# Thunder-Refix.net
KiCad netlist of a schematic drawn in Altium Designer
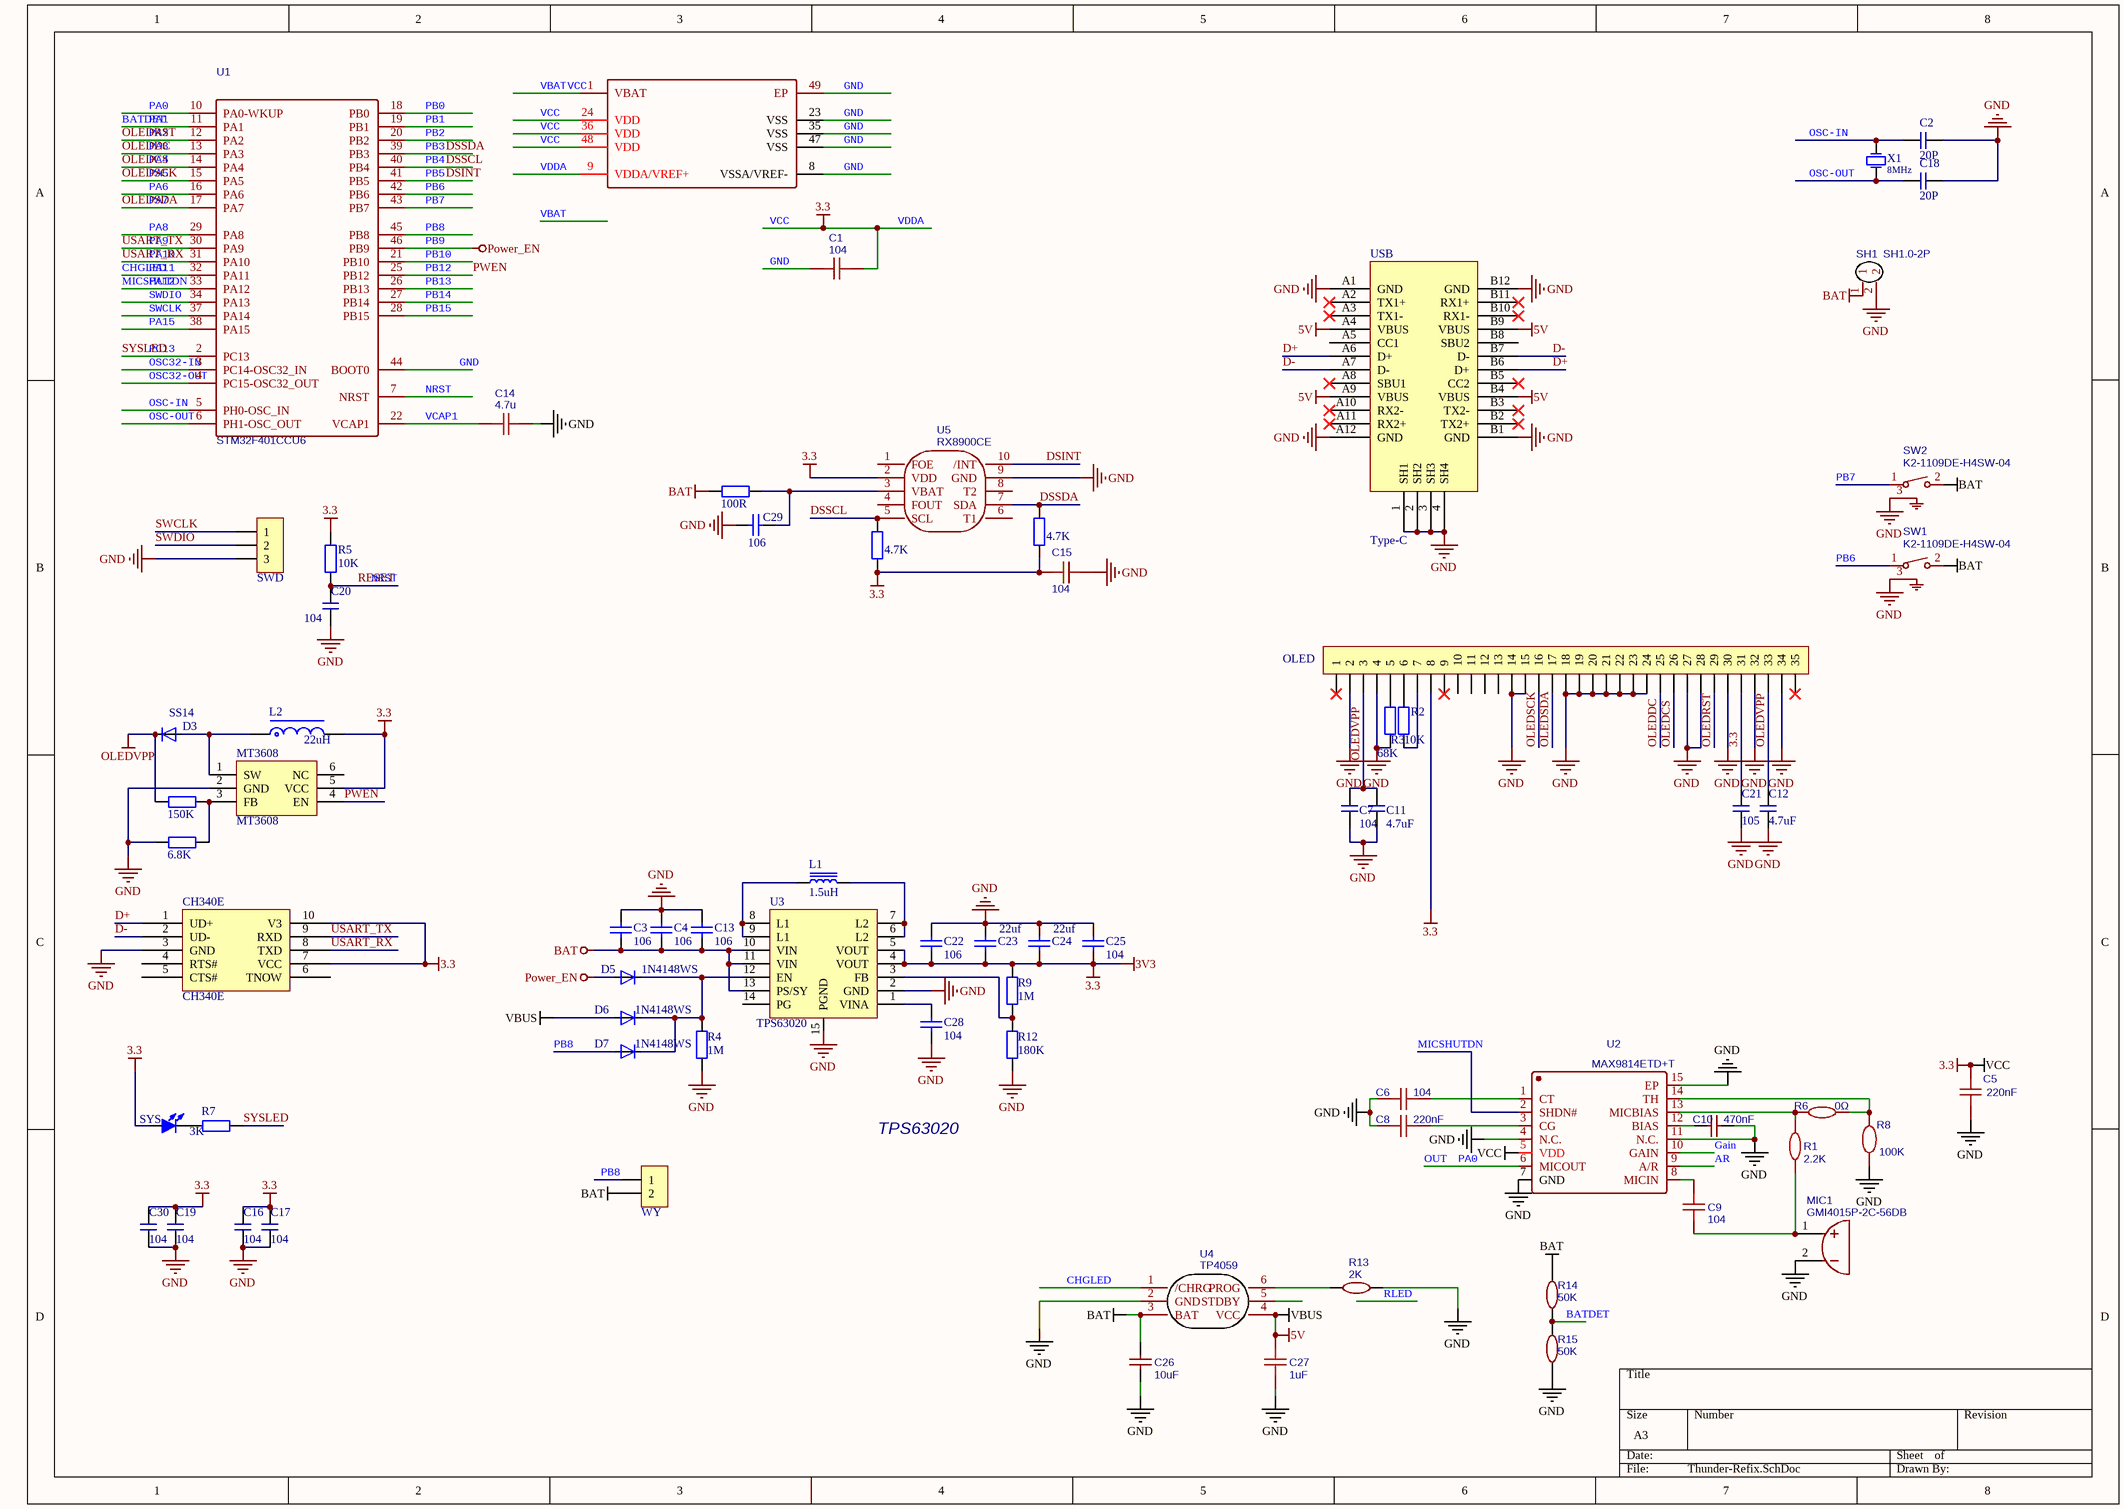
[diagram p0: Thunder-Refix.SchDoc]

(export (version "E")
  (design (tool "Eeschema 10.0.6"))
  (components
    (comp (ref "C1")
      (value "104")
      (footprint "0603C")
      (fields (field (name "CONTRIBUTOR") "LCEDA_Lib"))
      (libsource (lib "altium-import") (part "root_2_0.1u_"))
    )
    (comp (ref "C2") (value "20P") (footprint "0603C") (libsource (lib "Schlib1") (part "电容")))
    (comp (ref "C3")
      (value "106")
      (footprint "我的PCB库:0603c")
      (fields (field (name "C") "106"))
      (libsource (lib "元件库") (part "cap"))
    )
    (comp (ref "C4")
      (value "106")
      (footprint "我的PCB库:0603c")
      (fields (field (name "C") "106"))
      (libsource (lib "元件库") (part "cap"))
    )
    (comp (ref "C5")
      (value "220nF")
      (footprint "0603c")
      (fields
        (field (name "BOM_SUPPLIER PART") "C354366")
        (field (name "BOM_MANUFACTURER PART") "GCJ21BR71H224KA01L")
        (field (name "CONTRIBUTOR") "LCSC")
      )
      (libsource (lib "altium-import") (part "root_1_220nF_"))
    )
    (comp (ref "C6")
      (value "104")
      (footprint "0603c")
      (fields
        (field (name "BOM_SUPPLIER PART") "C444732")
        (field (name "BOM_MANUFACTURER PART") "FS055C104K4Z2A")
        (field (name "CONTRIBUTOR") "LCSC")
      )
      (libsource (lib "altium-import") (part "root_1_100nF_"))
    )
    (comp (ref "C7") (value "104") (footprint "0603C") (libsource (lib "Schlib1") (part "电容")))
    (comp (ref "C8")
      (value "220nF")
      (footprint "0603c")
      (fields
        (field (name "BOM_SUPPLIER PART") "C354366")
        (field (name "BOM_MANUFACTURER PART") "GCJ21BR71H224KA01L")
        (field (name "CONTRIBUTOR") "LCSC")
      )
      (libsource (lib "altium-import") (part "root_0_220nF_"))
    )
    (comp (ref "C9")
      (value "104")
      (footprint "0603c")
      (fields
        (field (name "BOM_SUPPLIER PART") "C444732")
        (field (name "BOM_MANUFACTURER PART") "FS055C104K4Z2A")
        (field (name "CONTRIBUTOR") "LCSC")
      )
      (libsource (lib "altium-import") (part "root_0_100nF_"))
    )
    (comp (ref "C10")
      (value "470nF")
      (footprint "0603c")
      (fields
        (field (name "BOM_MANUFACTURER PART") "CL21B474KBFNNNE")
        (field (name "BOM_SUPPLIER PART") "C13967")
      )
      (libsource (lib "altium-import") (part "root_0_470nF_"))
    )
    (comp (ref "C11") (value "4.7uF") (footprint "0603C") (libsource (lib "Schlib1") (part "电容")))
    (comp (ref "C12") (value "4.7uF") (footprint "0603C") (libsource (lib "Schlib1") (part "电容")))
    (comp (ref "C13")
      (value "106")
      (footprint "0603c")
      (fields (field (name "C") "106"))
      (libsource (lib "元件库") (part "cap"))
    )
    (comp (ref "C14")
      (value "4.7u")
      (footprint "0603C")
      (fields (field (name "CONTRIBUTOR") "LCEDA_Lib"))
      (libsource (lib "altium-import") (part "root_0_4.7u_"))
    )
    (comp (ref "C15")
      (value "104")
      (footprint "0603C")
      (fields (field (name "CONTRIBUTOR") "LCEDA_Lib"))
      (libsource (lib "altium-import") (part "root_0_0.1u_"))
    )
    (comp (ref "C16") (value "104") (footprint "0603C") (libsource (lib "Schlib1") (part "电容")))
    (comp (ref "C17") (value "104") (footprint "0603C") (libsource (lib "Schlib1") (part "电容")))
    (comp (ref "C18") (value "20P") (footprint "0603C") (libsource (lib "Schlib1") (part "电容")))
    (comp (ref "C19") (value "104") (footprint "0603C") (libsource (lib "Schlib1") (part "电容")))
    (comp (ref "C20") (value "104") (footprint "0603C") (libsource (lib "Schlib1") (part "电容")))
    (comp (ref "C21") (value "105") (footprint "0603C") (libsource (lib "Schlib1") (part "电容")))
    (comp (ref "C22")
      (value "106")
      (footprint "0603c")
      (fields (field (name "C") "106"))
      (libsource (lib "元件库") (part "cap"))
    )
    (comp (ref "C23")
      (value "22uf")
      (footprint "0603c")
      (fields (field (name "C") "22uf"))
      (libsource (lib "元件库") (part "cap"))
    )
    (comp (ref "C24")
      (value "22uf")
      (footprint "0603c")
      (fields (field (name "C") "22uf"))
      (libsource (lib "元件库") (part "cap"))
    )
    (comp (ref "C25")
      (value "104")
      (footprint "0603c")
      (fields (field (name "C") "104"))
      (libsource (lib "元件库") (part "cap"))
    )
    (comp (ref "C26")
      (value "10uF")
      (footprint "0603c")
      (fields
        (field (name "BOM_SUPPLIER PART") "C162317")
        (field (name "BOM_MANUFACTURER PART") "GRM21BB31C106KE15L")
        (field (name "CONTRIBUTOR") "LCSC")
      )
      (libsource (lib "altium-import") (part "root_1_10uF_"))
    )
    (comp (ref "C27")
      (value "1uF")
      (footprint "0603c")
      (fields
        (field (name "BOM_SUPPLIER PART") "C319195")
        (field (name "BOM_MANUFACTURER PART") "UMK212BJ105KG-T")
        (field (name "CONTRIBUTOR") "LCSC")
      )
      (libsource (lib "altium-import") (part "root_1_1uF_"))
    )
    (comp (ref "C28")
      (value "104")
      (footprint "0603c")
      (fields (field (name "C") "104"))
      (libsource (lib "元件库") (part "cap"))
    )
    (comp (ref "C29")
      (value "106")
      (footprint "0603c")
      (fields (field (name "C") "106"))
      (libsource (lib "元件库") (part "cap"))
    )
    (comp (ref "C30") (value "104") (footprint "0603C") (libsource (lib "Schlib1") (part "电容")))
    (comp (ref "CH340E") (value "CH340E") (footprint "MSOP10_L") (libsource (lib "CUBE_T1") (part "CH340E")))
    (comp (ref "D3")
      (value "SS14")
      (footprint "SOD323_1N4148WS")
      (description "Diode Switching 75V 0.3A 2-Pin SOD-323 T/R")
      (fields (field (name "MF") "ON Semiconductor") (field (name "MP") "1N4148WS"))
      (libsource (lib "1N4148WS") (part "1N4148WS"))
    )
    (comp (ref "D5")
      (value "1N4148WS")
      (footprint "SOD323_1N4148WS")
      (description "Diode Switching 75V 0.3A 2-Pin SOD-323 T/R")
      (fields (field (name "MF") "ON Semiconductor"))
      (libsource (lib "1N4148WS") (part "1N4148WS"))
    )
    (comp (ref "D6")
      (value "1N4148WS")
      (footprint "SOD323_1N4148WS")
      (description "Diode Switching 75V 0.3A 2-Pin SOD-323 T/R")
      (fields (field (name "MF") "ON Semiconductor"))
      (libsource (lib "1N4148WS") (part "1N4148WS"))
    )
    (comp (ref "D7")
      (value "1N4148WS")
      (footprint "SOD323_1N4148WS")
      (description "Diode Switching 75V 0.3A 2-Pin SOD-323 T/R")
      (fields (field (name "MF") "ON Semiconductor"))
      (libsource (lib "1N4148WS") (part "1N4148WS"))
    )
    (comp (ref "L1")
      (value "1.5uH")
      (footprint "我的PCB库:IND-SMD_L3.0-W3.0_NR3010")
      (fields (field (name "_VALUE") "1.5uH"))
      (libsource (lib "元件库") (part "Inductor Iron 2"))
    )
    (comp (ref "L2")
      (value "22uH")
      (footprint "IND-SMD_L3.0-W3.0_NR3010")
      (description "功率屏蔽电感")
      (fields (field (name "版权归属") "源创客"))
      (libsource (lib "3.1   - 电阻-电容-电感") (part "L-CDRH"))
    )
    (comp (ref "MIC1")
      (value "GMI4015P-2C-56DB")
      (footprint "MIC-TH_BD4.0-P2.00-D0.4-L-FD")
      (fields
        (field (name "BOM_SUPPLIER PART") "C233299")
        (field (name "BOM_MANUFACTURER PART") "GMI4015P-2C-56db")
        (field (name "CONTRIBUTOR") "LCSC")
      )
      (libsource (lib "altium-import") (part "root_0_GMI4015P-2C-56DB_"))
    )
    (comp (ref "MT3608")
      (value "MT3608")
      (footprint "SOT23-6N")
      (description "可调升压芯片")
      (fields (field (name "版权归属") "源创客"))
      (libsource (lib "1.3   - 电源类芯片") (part "SX1308"))
    )
    (comp (ref "OLED")
      (value "FPC1.0-35P")
      (footprint "1.69 OLED")
      (description "FPC连接器")
      (fields (field (name "版权归属") "源创客"))
      (libsource (lib "4.14 - FPC连接器") (part "FPC-35P"))
    )
    (comp (ref "R1")
      (value "2.2K")
      (footprint "0603r")
      (fields
        (field (name "BOM_SUPPLIER PART") "C325769")
        (field (name "BOM_MANUFACTURER PART") "RMC08052.2K1%N")
        (field (name "CONTRIBUTOR") "LCSC")
      )
      (libsource (lib "altium-import") (part "root_1_2.2K_"))
    )
    (comp (ref "R2")
      (value "10K")
      (footprint "0603R")
      (description "贴片电阻")
      (fields (field (name "版权归属") "源创客"))
      (libsource (lib "3.1   - 电阻-电容-电感") (part "R"))
    )
    (comp (ref "R3")
      (value "68K")
      (footprint "0603R")
      (description "贴片电阻")
      (fields (field (name "版权归属") "源创客"))
      (libsource (lib "3.1   - 电阻-电容-电感") (part "R"))
    )
    (comp (ref "R4")
      (value "1M")
      (footprint "0603r")
      (fields (field (name "R") "1M"))
      (libsource (lib "元件库") (part "Res"))
    )
    (comp (ref "R5")
      (value "10K")
      (footprint "0603R")
      (description "贴片电阻")
      (fields (field (name "版权归属") "源创客"))
      (libsource (lib "3.1   - 电阻-电容-电感") (part "R"))
    )
    (comp (ref "R6")
      (value "0Ω")
      (footprint "0603r")
      (fields
        (field (name "BOM_SUPPLIER PART") "C325765")
        (field (name "BOM_MANUFACTURER PART") "RMC0805150K1%N")
        (field (name "CONTRIBUTOR") "LCSC")
      )
      (libsource (lib "altium-import") (part "root_0_150K_"))
    )
    (comp (ref "R7")
      (value "3K")
      (footprint "0603R")
      (description "贴片电阻")
      (fields (field (name "版权归属") "源创客"))
      (libsource (lib "3.1   - 电阻-电容-电感") (part "R"))
    )
    (comp (ref "R8")
      (value "100K")
      (footprint "0603r")
      (fields
        (field (name "BOM_SUPPLIER PART") "C346756")
        (field (name "BOM_MANUFACTURER PART") "RTAN0805BKE100K")
        (field (name "CONTRIBUTOR") "LCSC")
      )
      (libsource (lib "altium-import") (part "root_1_100K_"))
    )
    (comp (ref "R9")
      (value "1M")
      (footprint "0603r")
      (fields (field (name "R") "1M"))
      (libsource (lib "元件库") (part "Res"))
    )
    (comp (ref "R10")
      (value "4.7K")
      (footprint "0603R")
      (description "贴片电阻")
      (fields (field (name "版权归属") "源创客"))
      (libsource (lib "3.1   - 电阻-电容-电感") (part "R"))
    )
    (comp (ref "R11")
      (value "4.7K")
      (footprint "0603R")
      (description "贴片电阻")
      (fields (field (name "版权归属") "源创客"))
      (libsource (lib "3.1   - 电阻-电容-电感") (part "R"))
    )
    (comp (ref "R12")
      (value "180K")
      (footprint "0603r")
      (fields (field (name "R") "180K"))
      (libsource (lib "元件库") (part "Res"))
    )
    (comp (ref "R13")
      (value "2K")
      (footprint "0603r")
      (fields
        (field (name "BOM_MANUFACTURER PART") "RC0603FR-071K5L")
        (field (name "BOM_SUPPLIER PART") "C114668")
      )
      (libsource (lib "altium-import") (part "root_0_1.5K_"))
    )
    (comp (ref "R14")
      (value "50K")
      (footprint "0603r")
      (fields
        (field (name "BOM_MANUFACTURER PART") "RC0603FR-071K5L")
        (field (name "BOM_SUPPLIER PART") "C114668")
      )
      (libsource (lib "altium-import") (part "root_1_1.5K_"))
    )
    (comp (ref "R15")
      (value "50K")
      (footprint "0603r")
      (fields
        (field (name "BOM_MANUFACTURER PART") "RC0603FR-071K5L")
        (field (name "BOM_SUPPLIER PART") "C114668")
      )
      (libsource (lib "altium-import") (part "root_1_1.5K_"))
    )
    (comp (ref "R16")
      (value "100R")
      (footprint "0603R")
      (description "贴片电阻")
      (fields (field (name "版权归属") "源创客"))
      (libsource (lib "3.1   - 电阻-电容-电感") (part "R"))
    )
    (comp (ref "RB")
      (value "150K")
      (footprint "0603R")
      (description "贴片电阻")
      (fields (field (name "版权归属") "源创客"))
      (libsource (lib "3.1   - 电阻-电容-电感") (part "R"))
    )
    (comp (ref "RS")
      (value "6.8K")
      (footprint "0603R")
      (description "贴片电阻")
      (fields (field (name "版权归属") "源创客"))
      (libsource (lib "3.1   - 电阻-电容-电感") (part "R"))
    )
    (comp (ref "SH1")
      (value "SH1.0-2P")
      (footprint "SH1.0")
      (fields (field (name "CONTRIBUTOR") "perry2867"))
      (libsource (lib "altium-import") (part "root_1_SH1.0-2P_"))
    )
    (comp (ref "SW1")
      (value "K2-1109DE-H4SW-04")
      (footprint "KEY-TH_K2-1109DE-CXXW-XX")
      (fields (field (name "BOM_SUPPLIER PART") "C961730") (field (name "CONTRIBUTOR") "LCSC"))
      (libsource (lib "altium-import") (part "root_0_K2-1109DE-H4SW-04_"))
    )
    (comp (ref "SW2")
      (value "K2-1109DE-H4SW-04")
      (footprint "KEY-TH_K2-1109DE-CXXW-XX")
      (fields (field (name "BOM_SUPPLIER PART") "C961730") (field (name "CONTRIBUTOR") "LCSC"))
      (libsource (lib "altium-import") (part "root_0_K2-1109DE-H4SW-04_"))
    )
    (comp (ref "SWD")
      (value "HDR-1X3")
      (footprint "ZH1.5-LI-3P")
      (description "3P接插件")
      (fields (field (name "版权归属") "源创客"))
      (libsource (lib "4.3   - 接插件-脚距1.5") (part "Header 3"))
    )
    (comp (ref "SYS")
      (value "粉色")
      (footprint "0603LED")
      (description "方形LED")
      (fields (field (name "版权归属") "源创客"))
      (libsource (lib "9.1   - LED") (part "LED-F234"))
    )
    (comp (ref "U1")
      (value "STM32F401CCU6")
      (footprint "qfn48")
      (fields (field (name "BOM_SUPPLIER PART") "C79861") (field (name "SUBPART_NO") "1"))
      (libsource (lib "Galaxy") (part "STM32F401CCU6"))
    )
    (comp (ref "U2")
      (value "MAX9814ETD+T")
      (footprint "TDFN-14_L3.0-W3.0-P0.40-BL-EP")
      (fields (field (name "BOM_SUPPLIER PART") "C41714"))
      (libsource (lib "altium-import") (part "root_0_MAX9814ETD+T_"))
    )
    (comp (ref "U3")
      (value "TPS63020")
      (footprint "我的PCB库:TPS63020")
      (libsource (lib "我的元件库") (part "TPS63020"))
    )
    (comp (ref "U4")
      (value "TP4059")
      (footprint "SOT23-6N")
      (fields (field (name "BOM_SUPPLIER PART") "C80364"))
      (libsource (lib "altium-import") (part "root_0_TP4059_"))
    )
    (comp (ref "U5")
      (value "RX8900CE")
      (footprint "RX8130")
      (fields (field (name "CONTRIBUTOR") "SudoMaker"))
      (libsource (lib "altium-import") (part "root_0_RX8900CE_"))
    )
    (comp (ref "USB") (value "Type-C") (footprint "Type-C") (libsource (lib "元件") (part "Type-C")))
    (comp (ref "WY")
      (value "HDR-1X2")
      (footprint "MX 1.25-WI-2P")
      (description "2P接插件")
      (fields (field (name "版权归属") "源创客"))
      (libsource (lib "4.2   - 接插件-脚距1.25") (part "Header 2"))
    )
    (comp (ref "X1")
      (value "8MHz")
      (footprint "OSC 5032-2P")
      (description "XTAL,8MHz,±20PPM,12.6*4.5")
      (fields (field (name "Comment") "1.6.1.01.005.001"))
      (libsource (lib "Mark_7") (part "1.6.1.01.005.001"))
    )
  )
  (nets
    (net (code "1") (name "/AR") (class "Default")
      (node (ref "U2") (pin "9") (pinfunction "A/R_9") (pintype "passive"))
    )
    (net (code "2") (name "/BATDET") (class "Default")
      (node (ref "R14") (pin "1") (pinfunction "1_1") (pintype "passive"))
      (node (ref "R15") (pin "2") (pinfunction "2_2") (pintype "passive"))
      (node (ref "U1") (pin "11") (pinfunction "PA1_11") (pintype "passive"))
    )
    (net (code "3") (name "/CHGLED") (class "Default")
      (node (ref "U1") (pin "32") (pinfunction "PA11_32") (pintype "passive"))
      (node (ref "U4") (pin "1") (pinfunction "/CHRG_1") (pintype "passive"))
    )
    (net (code "4") (name "/D+") (class "Default")
      (node (ref "CH340E") (pin "1") (pinfunction "UD+_1") (pintype "passive"))
      (node (ref "USB") (pin "A6") (pinfunction "D+_A6") (pintype "passive"))
      (node (ref "USB") (pin "B6") (pinfunction "D+_B6") (pintype "passive"))
    )
    (net (code "5") (name "/D-") (class "Default")
      (node (ref "CH340E") (pin "2") (pinfunction "UD-_2") (pintype "passive"))
      (node (ref "USB") (pin "A7") (pinfunction "D-_A7") (pintype "passive"))
      (node (ref "USB") (pin "B7") (pinfunction "D-_B7") (pintype "passive"))
    )
    (net (code "6") (name "/DSINT") (class "Default")
      (node (ref "U1") (pin "41") (pinfunction "PB5_41") (pintype "passive"))
      (node (ref "U5") (pin "10") (pinfunction "/INT_10") (pintype "passive"))
    )
    (net (code "7") (name "/DSSCL") (class "Default")
      (node (ref "R10") (pin "2") (pinfunction "2_2") (pintype "passive"))
      (node (ref "U1") (pin "40") (pinfunction "PB4_40") (pintype "passive"))
      (node (ref "U5") (pin "5") (pinfunction "SCL_5") (pintype "passive"))
    )
    (net (code "8") (name "/DSSDA") (class "Default")
      (node (ref "R11") (pin "1") (pinfunction "1_1") (pintype "passive"))
      (node (ref "U1") (pin "39") (pinfunction "PB3_39") (pintype "passive"))
      (node (ref "U5") (pin "7") (pinfunction "SDA_7") (pintype "passive"))
    )
    (net (code "9") (name "/Gain") (class "Default")
      (node (ref "U2") (pin "10") (pinfunction "GAIN_10") (pintype "passive"))
    )
    (net (code "10") (name "/MICSHUTDN") (class "Default")
      (node (ref "U1") (pin "33") (pinfunction "PA12_33") (pintype "passive"))
      (node (ref "U2") (pin "2") (pinfunction "SHDN#_2") (pintype "passive"))
    )
    (net (code "11") (name "/NRST") (class "Default")
      (node (ref "C20") (pin "1") (pinfunction "1_1") (pintype "passive"))
      (node (ref "R5") (pin "2") (pinfunction "2_2") (pintype "passive"))
      (node (ref "U1") (pin "7") (pinfunction "NRST_7") (pintype "passive"))
    )
    (net (code "12") (name "/OLEDCS") (class "Default")
      (node (ref "OLED") (pin "26") (pinfunction "26_26") (pintype "passive"))
      (node (ref "U1") (pin "14") (pinfunction "PA4_14") (pintype "passive"))
    )
    (net (code "13") (name "/OLEDDC") (class "Default")
      (node (ref "OLED") (pin "25") (pinfunction "25_25") (pintype "passive"))
      (node (ref "U1") (pin "13") (pinfunction "PA3_13") (pintype "passive"))
    )
    (net (code "14") (name "/OLEDRST") (class "Default")
      (node (ref "OLED") (pin "29") (pinfunction "29_29") (pintype "passive"))
      (node (ref "U1") (pin "12") (pinfunction "PA2_12") (pintype "passive"))
    )
    (net (code "15") (name "/OLEDSCK") (class "Default")
      (node (ref "OLED") (pin "16") (pinfunction "16_16") (pintype "passive"))
      (node (ref "U1") (pin "15") (pinfunction "PA5_15") (pintype "passive"))
    )
    (net (code "16") (name "/OLEDSDA") (class "Default")
      (node (ref "OLED") (pin "17") (pinfunction "17_17") (pintype "passive"))
      (node (ref "U1") (pin "17") (pinfunction "PA7_17") (pintype "passive"))
    )
    (net (code "17") (name "/OSC-IN") (class "Default")
      (node (ref "C2") (pin "2") (pinfunction "2_2") (pintype "passive"))
      (node (ref "U1") (pin "5") (pinfunction "PH0-OSC_IN_5") (pintype "passive"))
      (node (ref "X1") (pin "1") (pinfunction "OSC1_1") (pintype "passive"))
    )
    (net (code "18") (name "/OSC-OUT") (class "Default")
      (node (ref "C18") (pin "2") (pinfunction "2_2") (pintype "passive"))
      (node (ref "U1") (pin "6") (pinfunction "PH1-OSC_OUT_6") (pintype "passive"))
      (node (ref "X1") (pin "2") (pinfunction "OSC2_2") (pintype "passive"))
    )
    (net (code "19") (name "/OSC32-IN") (class "Default")
      (node (ref "U1") (pin "3") (pinfunction "PC14-OSC32_IN_3") (pintype "passive"))
    )
    (net (code "20") (name "/OSC32-OUT") (class "Default")
      (node (ref "U1") (pin "4") (pinfunction "PC15-OSC32_OUT_4") (pintype "passive"))
    )
    (net (code "21") (name "/OUT") (class "Default")
      (node (ref "U1") (pin "10") (pinfunction "PA0-WKUP_10") (pintype "passive"))
      (node (ref "U2") (pin "6") (pinfunction "MICOUT_6") (pintype "passive"))
    )
    (net (code "22") (name "/PA6") (class "Default")
      (node (ref "U1") (pin "16") (pinfunction "PA6_16") (pintype "passive"))
    )
    (net (code "23") (name "/PA8") (class "Default")
      (node (ref "U1") (pin "29") (pinfunction "PA8_29") (pintype "passive"))
    )
    (net (code "24") (name "/PA9") (class "Default")
      (node (ref "CH340E") (pin "9") (pinfunction "RXD_9") (pintype "passive"))
      (node (ref "U1") (pin "30") (pinfunction "PA9_30") (pintype "passive"))
    )
    (net (code "25") (name "/PA10") (class "Default")
      (node (ref "CH340E") (pin "8") (pinfunction "TXD_8") (pintype "passive"))
      (node (ref "U1") (pin "31") (pinfunction "PA10_31") (pintype "passive"))
    )
    (net (code "26") (name "/PA15") (class "Default")
      (node (ref "U1") (pin "38") (pinfunction "PA15_38") (pintype "passive"))
    )
    (net (code "27") (name "/PB0") (class "Default")
      (node (ref "U1") (pin "18") (pinfunction "PB0_18") (pintype "passive"))
    )
    (net (code "28") (name "/PB1") (class "Default")
      (node (ref "U1") (pin "19") (pinfunction "PB1_19") (pintype "passive"))
    )
    (net (code "29") (name "/PB2") (class "Default")
      (node (ref "U1") (pin "20") (pinfunction "PB2_20") (pintype "passive"))
    )
    (net (code "30") (name "/PB6") (class "Default")
      (node (ref "SW1") (pin "1") (pinfunction "1_1") (pintype "passive"))
      (node (ref "U1") (pin "42") (pinfunction "PB6_42") (pintype "passive"))
    )
    (net (code "31") (name "/PB7") (class "Default")
      (node (ref "SW2") (pin "1") (pinfunction "1_1") (pintype "passive"))
      (node (ref "U1") (pin "43") (pinfunction "PB7_43") (pintype "passive"))
    )
    (net (code "32") (name "/PB8") (class "Default")
      (node (ref "D7") (pin "A") (pinfunction "A_A") (pintype "passive"))
      (node (ref "U1") (pin "45") (pinfunction "PB8_45") (pintype "passive"))
      (node (ref "WY") (pin "1") (pinfunction "1_1") (pintype "passive"))
    )
    (net (code "33") (name "/PB10") (class "Default")
      (node (ref "U1") (pin "21") (pinfunction "PB10_21") (pintype "passive"))
    )
    (net (code "34") (name "/PB12") (class "Default")
      (node (ref "MT3608") (pin "4") (pinfunction "EN_4") (pintype "passive"))
      (node (ref "U1") (pin "25") (pinfunction "PB12_25") (pintype "passive"))
    )
    (net (code "35") (name "/PB13") (class "Default")
      (node (ref "U1") (pin "26") (pinfunction "PB13_26") (pintype "passive"))
    )
    (net (code "36") (name "/PB14") (class "Default")
      (node (ref "U1") (pin "27") (pinfunction "PB14_27") (pintype "passive"))
    )
    (net (code "37") (name "/PB15") (class "Default")
      (node (ref "U1") (pin "28") (pinfunction "PB15_28") (pintype "passive"))
    )
    (net (code "38") (name "/PC13") (class "Default")
      (node (ref "R7") (pin "1") (pinfunction "1_1") (pintype "passive"))
      (node (ref "U1") (pin "2") (pinfunction "PC13_2") (pintype "passive"))
    )
    (net (code "40") (name "/SWCLK") (class "Default")
      (node (ref "SWD") (pin "1") (pinfunction "1_1") (pintype "passive"))
      (node (ref "U1") (pin "37") (pinfunction "PA14_37") (pintype "passive"))
    )
    (net (code "41") (name "/SWDIO") (class "Default")
      (node (ref "SWD") (pin "2") (pinfunction "2_2") (pintype "passive"))
      (node (ref "U1") (pin "34") (pinfunction "PA13_34") (pintype "passive"))
    )
    (net (code "42") (name "/VCAP1") (class "Default")
      (node (ref "C14") (pin "1") (pinfunction "1_1") (pintype "passive"))
      (node (ref "U1") (pin "22") (pinfunction "VCAP1_22") (pintype "passive"))
    )
    (net (code "43") (name "3.3") (class "Default")
      (node (ref "C1") (pin "1") (pinfunction "1_1") (pintype "passive"))
      (node (ref "C15") (pin "1") (pinfunction "1_1") (pintype "passive"))
      (node (ref "C16") (pin "1") (pinfunction "1_1") (pintype "passive"))
      (node (ref "C17") (pin "1") (pinfunction "1_1") (pintype "passive"))
      (node (ref "C19") (pin "1") (pinfunction "1_1") (pintype "passive"))
      (node (ref "C21") (pin "1") (pinfunction "1_1") (pintype "passive"))
      (node (ref "C22") (pin "1") (pinfunction "1_1") (pintype "passive"))
      (node (ref "C23") (pin "1") (pinfunction "1_1") (pintype "passive"))
      (node (ref "C24") (pin "1") (pinfunction "1_1") (pintype "passive"))
      (node (ref "C25") (pin "1") (pinfunction "1_1") (pintype "passive"))
      (node (ref "C30") (pin "1") (pinfunction "1_1") (pintype "passive"))
      (node (ref "C5") (pin "2") (pinfunction "2_2") (pintype "passive"))
      (node (ref "CH340E") (pin "10") (pinfunction "V3_10") (pintype "passive"))
      (node (ref "CH340E") (pin "7") (pinfunction "VCC_7") (pintype "passive"))
      (node (ref "L2") (pin "2") (pinfunction "2_2") (pintype "passive"))
      (node (ref "MT3608") (pin "5") (pinfunction "VCC_5") (pintype "passive"))
      (node (ref "OLED") (pin "31") (pinfunction "31_31") (pintype "passive"))
      (node (ref "OLED") (pin "8") (pinfunction "8_8") (pintype "passive"))
      (node (ref "R10") (pin "1") (pinfunction "1_1") (pintype "passive"))
      (node (ref "R11") (pin "2") (pinfunction "2_2") (pintype "passive"))
      (node (ref "R5") (pin "1") (pinfunction "1_1") (pintype "passive"))
      (node (ref "R9") (pin "1") (pinfunction "1_1") (pintype "passive"))
      (node (ref "SYS") (pin "1") (pinfunction "A_1") (pintype "passive"))
      (node (ref "U1") (pin "1") (pinfunction "VBAT_1") (pintype "passive"))
      (node (ref "U1") (pin "24") (pinfunction "VDD_24") (pintype "passive"))
      (node (ref "U1") (pin "36") (pinfunction "VDD_36") (pintype "passive"))
      (node (ref "U1") (pin "48") (pinfunction "VDD_48") (pintype "passive"))
      (node (ref "U1") (pin "9") (pinfunction "VDDA/VREF+_9") (pintype "passive"))
      (node (ref "U2") (pin "5") (pinfunction "VDD_5") (pintype "passive"))
      (node (ref "U3") (pin "4") (pinfunction "VOUT_4") (pintype "passive"))
      (node (ref "U3") (pin "5") (pinfunction "VOUT_5") (pintype "passive"))
      (node (ref "U5") (pin "2") (pinfunction "VDD_2") (pintype "passive"))
    )
    (net (code "44") (name "5V") (class "Default")
      (node (ref "C27") (pin "1") (pinfunction "1_1") (pintype "passive"))
      (node (ref "D6") (pin "A") (pinfunction "A_A") (pintype "passive"))
      (node (ref "U4") (pin "4") (pinfunction "VCC_4") (pintype "passive"))
      (node (ref "USB") (pin "A4") (pinfunction "VBUS_A4") (pintype "passive"))
      (node (ref "USB") (pin "A9") (pinfunction "VBUS_A9") (pintype "passive"))
      (node (ref "USB") (pin "B4") (pinfunction "VBUS_B4") (pintype "passive"))
      (node (ref "USB") (pin "B9") (pinfunction "VBUS_B9") (pintype "passive"))
    )
    (net (code "45") (name "BAT") (class "Default")
      (node (ref "C13") (pin "1") (pinfunction "1_1") (pintype "passive"))
      (node (ref "C26") (pin "2") (pinfunction "2_2") (pintype "passive"))
      (node (ref "C3") (pin "1") (pinfunction "1_1") (pintype "passive"))
      (node (ref "C4") (pin "1") (pinfunction "1_1") (pintype "passive"))
      (node (ref "R14") (pin "2") (pinfunction "2_2") (pintype "passive"))
      (node (ref "R16") (pin "2") (pinfunction "2_2") (pintype "passive"))
      (node (ref "SH1") (pin "1") (pinfunction "1_1") (pintype "passive"))
      (node (ref "SW1") (pin "2") (pinfunction "2_2") (pintype "passive"))
      (node (ref "SW2") (pin "2") (pinfunction "2_2") (pintype "passive"))
      (node (ref "U3") (pin "10") (pinfunction "VIN_10") (pintype "passive"))
      (node (ref "U3") (pin "11") (pinfunction "VIN_11") (pintype "passive"))
      (node (ref "U3") (pin "13") (pinfunction "PS/SY_13") (pintype "passive"))
      (node (ref "U4") (pin "3") (pinfunction "BAT_3") (pintype "passive"))
      (node (ref "WY") (pin "2") (pinfunction "2_2") (pintype "passive"))
    )
    (net (code "46") (name "GND") (class "Default")
      (node (ref "C1") (pin "2") (pinfunction "2_2") (pintype "passive"))
      (node (ref "C10") (pin "2") (pinfunction "2_2") (pintype "passive"))
      (node (ref "C11") (pin "2") (pinfunction "2_2") (pintype "passive"))
      (node (ref "C12") (pin "2") (pinfunction "2_2") (pintype "passive"))
      (node (ref "C13") (pin "2") (pinfunction "2_2") (pintype "passive"))
      (node (ref "C14") (pin "2") (pinfunction "2_2") (pintype "passive"))
      (node (ref "C15") (pin "2") (pinfunction "2_2") (pintype "passive"))
      (node (ref "C16") (pin "2") (pinfunction "2_2") (pintype "passive"))
      (node (ref "C17") (pin "2") (pinfunction "2_2") (pintype "passive"))
      (node (ref "C18") (pin "1") (pinfunction "1_1") (pintype "passive"))
      (node (ref "C19") (pin "2") (pinfunction "2_2") (pintype "passive"))
      (node (ref "C2") (pin "1") (pinfunction "1_1") (pintype "passive"))
      (node (ref "C20") (pin "2") (pinfunction "2_2") (pintype "passive"))
      (node (ref "C21") (pin "2") (pinfunction "2_2") (pintype "passive"))
      (node (ref "C22") (pin "2") (pinfunction "2_2") (pintype "passive"))
      (node (ref "C23") (pin "2") (pinfunction "2_2") (pintype "passive"))
      (node (ref "C24") (pin "2") (pinfunction "2_2") (pintype "passive"))
      (node (ref "C25") (pin "2") (pinfunction "2_2") (pintype "passive"))
      (node (ref "C26") (pin "1") (pinfunction "1_1") (pintype "passive"))
      (node (ref "C27") (pin "2") (pinfunction "2_2") (pintype "passive"))
      (node (ref "C28") (pin "1") (pinfunction "1_1") (pintype "passive"))
      (node (ref "C29") (pin "2") (pinfunction "2_2") (pintype "passive"))
      (node (ref "C3") (pin "2") (pinfunction "2_2") (pintype "passive"))
      (node (ref "C30") (pin "2") (pinfunction "2_2") (pintype "passive"))
      (node (ref "C4") (pin "2") (pinfunction "2_2") (pintype "passive"))
      (node (ref "C5") (pin "1") (pinfunction "1_1") (pintype "passive"))
      (node (ref "C6") (pin "1") (pinfunction "1_1") (pintype "passive"))
      (node (ref "C7") (pin "2") (pinfunction "2_2") (pintype "passive"))
      (node (ref "C8") (pin "1") (pinfunction "1_1") (pintype "passive"))
      (node (ref "CH340E") (pin "3") (pinfunction "GND_3") (pintype "passive"))
      (node (ref "MIC1") (pin "2") (pinfunction "2_2") (pintype "passive"))
      (node (ref "MT3608") (pin "2") (pinfunction "GND_2") (pintype "passive"))
      (node (ref "OLED") (pin "14") (pinfunction "14_14") (pintype "passive"))
      (node (ref "OLED") (pin "15") (pinfunction "15_15") (pintype "passive"))
      (node (ref "OLED") (pin "18") (pinfunction "18_18") (pintype "passive"))
      (node (ref "OLED") (pin "19") (pinfunction "19_19") (pintype "passive"))
      (node (ref "OLED") (pin "2") (pinfunction "2_2") (pintype "passive"))
      (node (ref "OLED") (pin "20") (pinfunction "20_20") (pintype "passive"))
      (node (ref "OLED") (pin "21") (pinfunction "21_21") (pintype "passive"))
      (node (ref "OLED") (pin "22") (pinfunction "22_22") (pintype "passive"))
      (node (ref "OLED") (pin "23") (pinfunction "23_23") (pintype "passive"))
      (node (ref "OLED") (pin "24") (pinfunction "24_24") (pintype "passive"))
      (node (ref "OLED") (pin "27") (pinfunction "27_27") (pintype "passive"))
      (node (ref "OLED") (pin "28") (pinfunction "28_28") (pintype "passive"))
      (node (ref "OLED") (pin "30") (pinfunction "30_30") (pintype "passive"))
      (node (ref "OLED") (pin "32") (pinfunction "32_32") (pintype "passive"))
      (node (ref "OLED") (pin "34") (pinfunction "34_34") (pintype "passive"))
      (node (ref "OLED") (pin "4") (pinfunction "4_4") (pintype "passive"))
      (node (ref "R12") (pin "2") (pinfunction "2_2") (pintype "passive"))
      (node (ref "R13") (pin "2") (pinfunction "2_2") (pintype "passive"))
      (node (ref "R15") (pin "1") (pinfunction "1_1") (pintype "passive"))
      (node (ref "R3") (pin "1") (pinfunction "1_1") (pintype "passive"))
      (node (ref "R4") (pin "2") (pinfunction "2_2") (pintype "passive"))
      (node (ref "R8") (pin "1") (pinfunction "1_1") (pintype "passive"))
      (node (ref "RS") (pin "1") (pinfunction "1_1") (pintype "passive"))
      (node (ref "SH1") (pin "2") (pinfunction "2_2") (pintype "passive"))
      (node (ref "SW1") (pin "3") (pinfunction "GND_3") (pintype "passive"))
      (node (ref "SW2") (pin "3") (pinfunction "GND_3") (pintype "passive"))
      (node (ref "SWD") (pin "3") (pinfunction "3_3") (pintype "passive"))
      (node (ref "U1") (pin "23") (pinfunction "VSS_23") (pintype "passive"))
      (node (ref "U1") (pin "35") (pinfunction "VSS_35") (pintype "passive"))
      (node (ref "U1") (pin "44") (pinfunction "BOOT0_44") (pintype "passive"))
      (node (ref "U1") (pin "47") (pinfunction "VSS_47") (pintype "passive"))
      (node (ref "U1") (pin "49") (pinfunction "EP_49") (pintype "passive"))
      (node (ref "U1") (pin "8") (pinfunction "VSSA/VREF-_8") (pintype "passive"))
      (node (ref "U2") (pin "11") (pinfunction "N.C._11") (pintype "passive"))
      (node (ref "U2") (pin "15") (pinfunction "EP_15") (pintype "passive"))
      (node (ref "U2") (pin "4") (pinfunction "N.C._4") (pintype "passive"))
      (node (ref "U2") (pin "7") (pinfunction "GND_7") (pintype "passive"))
      (node (ref "U3") (pin "15") (pinfunction "PGND_15") (pintype "passive"))
      (node (ref "U3") (pin "2") (pinfunction "GND_2") (pintype "passive"))
      (node (ref "U4") (pin "2") (pinfunction "GND_2") (pintype "passive"))
      (node (ref "U5") (pin "9") (pinfunction "GND_9") (pintype "passive"))
      (node (ref "USB") (pin "1") (pinfunction "SH1_1") (pintype "passive"))
      (node (ref "USB") (pin "2") (pinfunction "SH2_2") (pintype "passive"))
      (node (ref "USB") (pin "3") (pinfunction "SH3_3") (pintype "passive"))
      (node (ref "USB") (pin "4") (pinfunction "SH4_4") (pintype "passive"))
      (node (ref "USB") (pin "A1") (pinfunction "GND_A1") (pintype "passive"))
      (node (ref "USB") (pin "A12") (pinfunction "GND_A12") (pintype "passive"))
      (node (ref "USB") (pin "B1") (pinfunction "GND_B1") (pintype "passive"))
      (node (ref "USB") (pin "B12") (pinfunction "GND_B12") (pintype "passive"))
    )
    (net (code "47") (name "Net-(C9-Pad2)") (class "Default")
      (node (ref "C9") (pin "2") (pinfunction "2_2") (pintype "passive"))
      (node (ref "MIC1") (pin "1") (pinfunction "1_1") (pintype "passive"))
      (node (ref "R1") (pin "1") (pinfunction "1_1") (pintype "passive"))
    )
    (net (code "48") (name "Net-(L1-Pad1)") (class "Default")
      (node (ref "L1") (pin "1") (pinfunction "1_1") (pintype "passive"))
      (node (ref "U3") (pin "8") (pinfunction "L1_8") (pintype "passive"))
      (node (ref "U3") (pin "9") (pinfunction "L1_9") (pintype "passive"))
    )
    (net (code "49") (name "Net-(L1-Pad2)") (class "Default")
      (node (ref "L1") (pin "2") (pinfunction "2_2") (pintype "passive"))
      (node (ref "U3") (pin "6") (pinfunction "L2_6") (pintype "passive"))
      (node (ref "U3") (pin "7") (pinfunction "L2_7") (pintype "passive"))
    )
    (net (code "50") (name "Net-(MT3608-FB)") (class "Default")
      (node (ref "MT3608") (pin "3") (pinfunction "FB_3") (pintype "passive"))
      (node (ref "RB") (pin "2") (pinfunction "2_2") (pintype "passive"))
      (node (ref "RS") (pin "2") (pinfunction "2_2") (pintype "passive"))
    )
    (net (code "51") (name "Net-(MT3608-SW)") (class "Default")
      (node (ref "D3") (pin "A") (pinfunction "A_A") (pintype "passive"))
      (node (ref "L2") (pin "1") (pinfunction "1_1") (pintype "passive"))
      (node (ref "MT3608") (pin "1") (pinfunction "SW_1") (pintype "passive"))
    )
    (net (code "52") (name "Net-(OLED-Pad5)") (class "Default")
      (node (ref "OLED") (pin "5") (pinfunction "5_5") (pintype "passive"))
      (node (ref "R3") (pin "2") (pinfunction "2_2") (pintype "passive"))
    )
    (net (code "53") (name "Net-(OLED-Pad6)") (class "Default")
      (node (ref "OLED") (pin "6") (pinfunction "6_6") (pintype "passive"))
      (node (ref "R2") (pin "2") (pinfunction "2_2") (pintype "passive"))
    )
    (net (code "54") (name "Net-(OLED-Pad7)") (class "Default")
      (node (ref "OLED") (pin "7") (pinfunction "7_7") (pintype "passive"))
      (node (ref "R2") (pin "1") (pinfunction "1_1") (pintype "passive"))
    )
    (net (code "55") (name "Net-(SYS-K)") (class "Default")
      (node (ref "R7") (pin "2") (pinfunction "2_2") (pintype "passive"))
      (node (ref "SYS") (pin "2") (pinfunction "K_2") (pintype "passive"))
    )
    (net (code "56") (name "Net-(U2-BIAS)") (class "Default")
      (node (ref "C10") (pin "1") (pinfunction "1_1") (pintype "passive"))
      (node (ref "U2") (pin "12") (pinfunction "BIAS_12") (pintype "passive"))
    )
    (net (code "57") (name "Net-(U2-CG)") (class "Default")
      (node (ref "C8") (pin "2") (pinfunction "2_2") (pintype "passive"))
      (node (ref "U2") (pin "3") (pinfunction "CG_3") (pintype "passive"))
    )
    (net (code "58") (name "Net-(U2-CT)") (class "Default")
      (node (ref "C6") (pin "2") (pinfunction "2_2") (pintype "passive"))
      (node (ref "U2") (pin "1") (pinfunction "CT_1") (pintype "passive"))
    )
    (net (code "59") (name "Net-(U2-MICBIAS)") (class "Default")
      (node (ref "R1") (pin "2") (pinfunction "2_2") (pintype "passive"))
      (node (ref "R6") (pin "1") (pinfunction "1_1") (pintype "passive"))
      (node (ref "U2") (pin "13") (pinfunction "MICBIAS_13") (pintype "passive"))
    )
    (net (code "60") (name "Net-(U2-MICIN)") (class "Default")
      (node (ref "C9") (pin "1") (pinfunction "1_1") (pintype "passive"))
      (node (ref "U2") (pin "8") (pinfunction "MICIN_8") (pintype "passive"))
    )
    (net (code "61") (name "Net-(U2-TH)") (class "Default")
      (node (ref "R6") (pin "2") (pinfunction "2_2") (pintype "passive"))
      (node (ref "R8") (pin "2") (pinfunction "2_2") (pintype "passive"))
      (node (ref "U2") (pin "14") (pinfunction "TH_14") (pintype "passive"))
    )
    (net (code "62") (name "Net-(U3-EN)") (class "Default")
      (node (ref "D5") (pin "C") (pinfunction "C_C") (pintype "passive"))
      (node (ref "D6") (pin "C") (pinfunction "C_C") (pintype "passive"))
      (node (ref "D7") (pin "C") (pinfunction "C_C") (pintype "passive"))
      (node (ref "R4") (pin "1") (pinfunction "1_1") (pintype "passive"))
      (node (ref "U3") (pin "12") (pinfunction "EN_12") (pintype "passive"))
    )
    (net (code "63") (name "Net-(U3-FB)") (class "Default")
      (node (ref "R12") (pin "1") (pinfunction "1_1") (pintype "passive"))
      (node (ref "R9") (pin "2") (pinfunction "2_2") (pintype "passive"))
      (node (ref "U3") (pin "3") (pinfunction "FB_3") (pintype "passive"))
    )
    (net (code "64") (name "Net-(U3-VINA)") (class "Default")
      (node (ref "C28") (pin "2") (pinfunction "2_2") (pintype "passive"))
      (node (ref "U3") (pin "1") (pinfunction "VINA_1") (pintype "passive"))
    )
    (net (code "65") (name "Net-(U4-PROG)") (class "Default")
      (node (ref "R13") (pin "1") (pinfunction "1_1") (pintype "passive"))
      (node (ref "U4") (pin "6") (pinfunction "PROG_6") (pintype "passive"))
    )
    (net (code "66") (name "Net-(U5-VBAT)") (class "Default")
      (node (ref "C29") (pin "1") (pinfunction "1_1") (pintype "passive"))
      (node (ref "R16") (pin "1") (pinfunction "1_1") (pintype "passive"))
      (node (ref "U5") (pin "3") (pinfunction "VBAT_3") (pintype "passive"))
    )
    (net (code "67") (name "OLEDVPP") (class "Default")
      (node (ref "C11") (pin "1") (pinfunction "1_1") (pintype "passive"))
      (node (ref "C12") (pin "1") (pinfunction "1_1") (pintype "passive"))
      (node (ref "C7") (pin "1") (pinfunction "1_1") (pintype "passive"))
      (node (ref "D3") (pin "C") (pinfunction "C_C") (pintype "passive"))
      (node (ref "OLED") (pin "3") (pinfunction "3_3") (pintype "passive"))
      (node (ref "OLED") (pin "33") (pinfunction "33_33") (pintype "passive"))
      (node (ref "RB") (pin "1") (pinfunction "1_1") (pintype "passive"))
    )
    (net (code "68") (name "Power_EN") (class "Default")
      (node (ref "D5") (pin "A") (pinfunction "A_A") (pintype "passive"))
      (node (ref "U1") (pin "46") (pinfunction "PB9_46") (pintype "passive"))
    )
    (net (code "69") (name "unconnected-(CH340E-CTS#-Pad5)") (class "Default")
      (node (ref "CH340E") (pin "5") (pinfunction "CTS#_5") (pintype "passive"))
    )
    (net (code "70") (name "unconnected-(CH340E-RTS#-Pad4)") (class "Default")
      (node (ref "CH340E") (pin "4") (pinfunction "RTS#_4") (pintype "passive"))
    )
    (net (code "71") (name "unconnected-(CH340E-TNOW-Pad6)") (class "Default")
      (node (ref "CH340E") (pin "6") (pinfunction "TNOW_6") (pintype "passive"))
    )
    (net (code "72") (name "unconnected-(MT3608-NC-Pad6)") (class "Default")
      (node (ref "MT3608") (pin "6") (pinfunction "NC_6") (pintype "passive"))
    )
    (net (code "73") (name "unconnected-(OLED-Pad1)") (class "Default")
      (node (ref "OLED") (pin "1") (pinfunction "1_1") (pintype "passive+no_connect"))
    )
    (net (code "74") (name "unconnected-(OLED-Pad9)") (class "Default")
      (node (ref "OLED") (pin "9") (pinfunction "9_9") (pintype "passive+no_connect"))
    )
    (net (code "75") (name "unconnected-(OLED-Pad10)") (class "Default")
      (node (ref "OLED") (pin "10") (pinfunction "10_10") (pintype "passive"))
    )
    (net (code "76") (name "unconnected-(OLED-Pad11)") (class "Default")
      (node (ref "OLED") (pin "11") (pinfunction "11_11") (pintype "passive"))
    )
    (net (code "77") (name "unconnected-(OLED-Pad12)") (class "Default")
      (node (ref "OLED") (pin "12") (pinfunction "12_12") (pintype "passive"))
    )
    (net (code "78") (name "unconnected-(OLED-Pad13)") (class "Default")
      (node (ref "OLED") (pin "13") (pinfunction "13_13") (pintype "passive"))
    )
    (net (code "79") (name "unconnected-(OLED-Pad35)") (class "Default")
      (node (ref "OLED") (pin "35") (pinfunction "35_35") (pintype "passive+no_connect"))
    )
    (net (code "80") (name "unconnected-(U3-PG-Pad14)") (class "Default")
      (node (ref "U3") (pin "14") (pinfunction "PG_14") (pintype "passive"))
    )
    (net (code "81") (name "unconnected-(U4-STDBY-Pad5)") (class "Default")
      (node (ref "U4") (pin "5") (pinfunction "STDBY_5") (pintype "passive"))
    )
    (net (code "82") (name "unconnected-(U5-FOE-Pad1)") (class "Default")
      (node (ref "U5") (pin "1") (pinfunction "FOE_1") (pintype "passive"))
    )
    (net (code "83") (name "unconnected-(U5-FOUT-Pad4)") (class "Default")
      (node (ref "U5") (pin "4") (pinfunction "FOUT_4") (pintype "passive"))
    )
    (net (code "84") (name "unconnected-(U5-T1-Pad6)") (class "Default")
      (node (ref "U5") (pin "6") (pinfunction "T1_6") (pintype "passive"))
    )
    (net (code "85") (name "unconnected-(U5-T2-Pad8)") (class "Default")
      (node (ref "U5") (pin "8") (pinfunction "T2_8") (pintype "passive"))
    )
    (net (code "86") (name "unconnected-(USB-CC1-PadA5)") (class "Default")
      (node (ref "USB") (pin "A5") (pinfunction "CC1_A5") (pintype "passive"))
    )
    (net (code "87") (name "unconnected-(USB-CC2-PadB5)") (class "Default")
      (node (ref "USB") (pin "B5") (pinfunction "CC2_B5") (pintype "passive+no_connect"))
    )
    (net (code "88") (name "unconnected-(USB-RX1+-PadB11)") (class "Default")
      (node (ref "USB") (pin "B11") (pinfunction "RX1+_B11") (pintype "passive+no_connect"))
    )
    (net (code "89") (name "unconnected-(USB-RX1--PadB10)") (class "Default")
      (node (ref "USB") (pin "B10") (pinfunction "RX1-_B10") (pintype "passive+no_connect"))
    )
    (net (code "90") (name "unconnected-(USB-RX2+-PadA11)") (class "Default")
      (node (ref "USB") (pin "A11") (pinfunction "RX2+_A11") (pintype "passive+no_connect"))
    )
    (net (code "91") (name "unconnected-(USB-RX2--PadA10)") (class "Default")
      (node (ref "USB") (pin "A10") (pinfunction "RX2-_A10") (pintype "passive+no_connect"))
    )
    (net (code "92") (name "unconnected-(USB-SBU1-PadA8)") (class "Default")
      (node (ref "USB") (pin "A8") (pinfunction "SBU1_A8") (pintype "passive+no_connect"))
    )
    (net (code "93") (name "unconnected-(USB-SBU2-PadB8)") (class "Default")
      (node (ref "USB") (pin "B8") (pinfunction "SBU2_B8") (pintype "passive"))
    )
    (net (code "94") (name "unconnected-(USB-TX1+-PadA2)") (class "Default")
      (node (ref "USB") (pin "A2") (pinfunction "TX1+_A2") (pintype "passive+no_connect"))
    )
    (net (code "95") (name "unconnected-(USB-TX1--PadA3)") (class "Default")
      (node (ref "USB") (pin "A3") (pinfunction "TX1-_A3") (pintype "passive+no_connect"))
    )
    (net (code "96") (name "unconnected-(USB-TX2+-PadB2)") (class "Default")
      (node (ref "USB") (pin "B2") (pinfunction "TX2+_B2") (pintype "passive+no_connect"))
    )
    (net (code "97") (name "unconnected-(USB-TX2--PadB3)") (class "Default")
      (node (ref "USB") (pin "B3") (pinfunction "TX2-_B3") (pintype "passive+no_connect"))
    )
  )
)
